# OpenLog.net
KiCad netlist of a schematic drawn in EAGLE
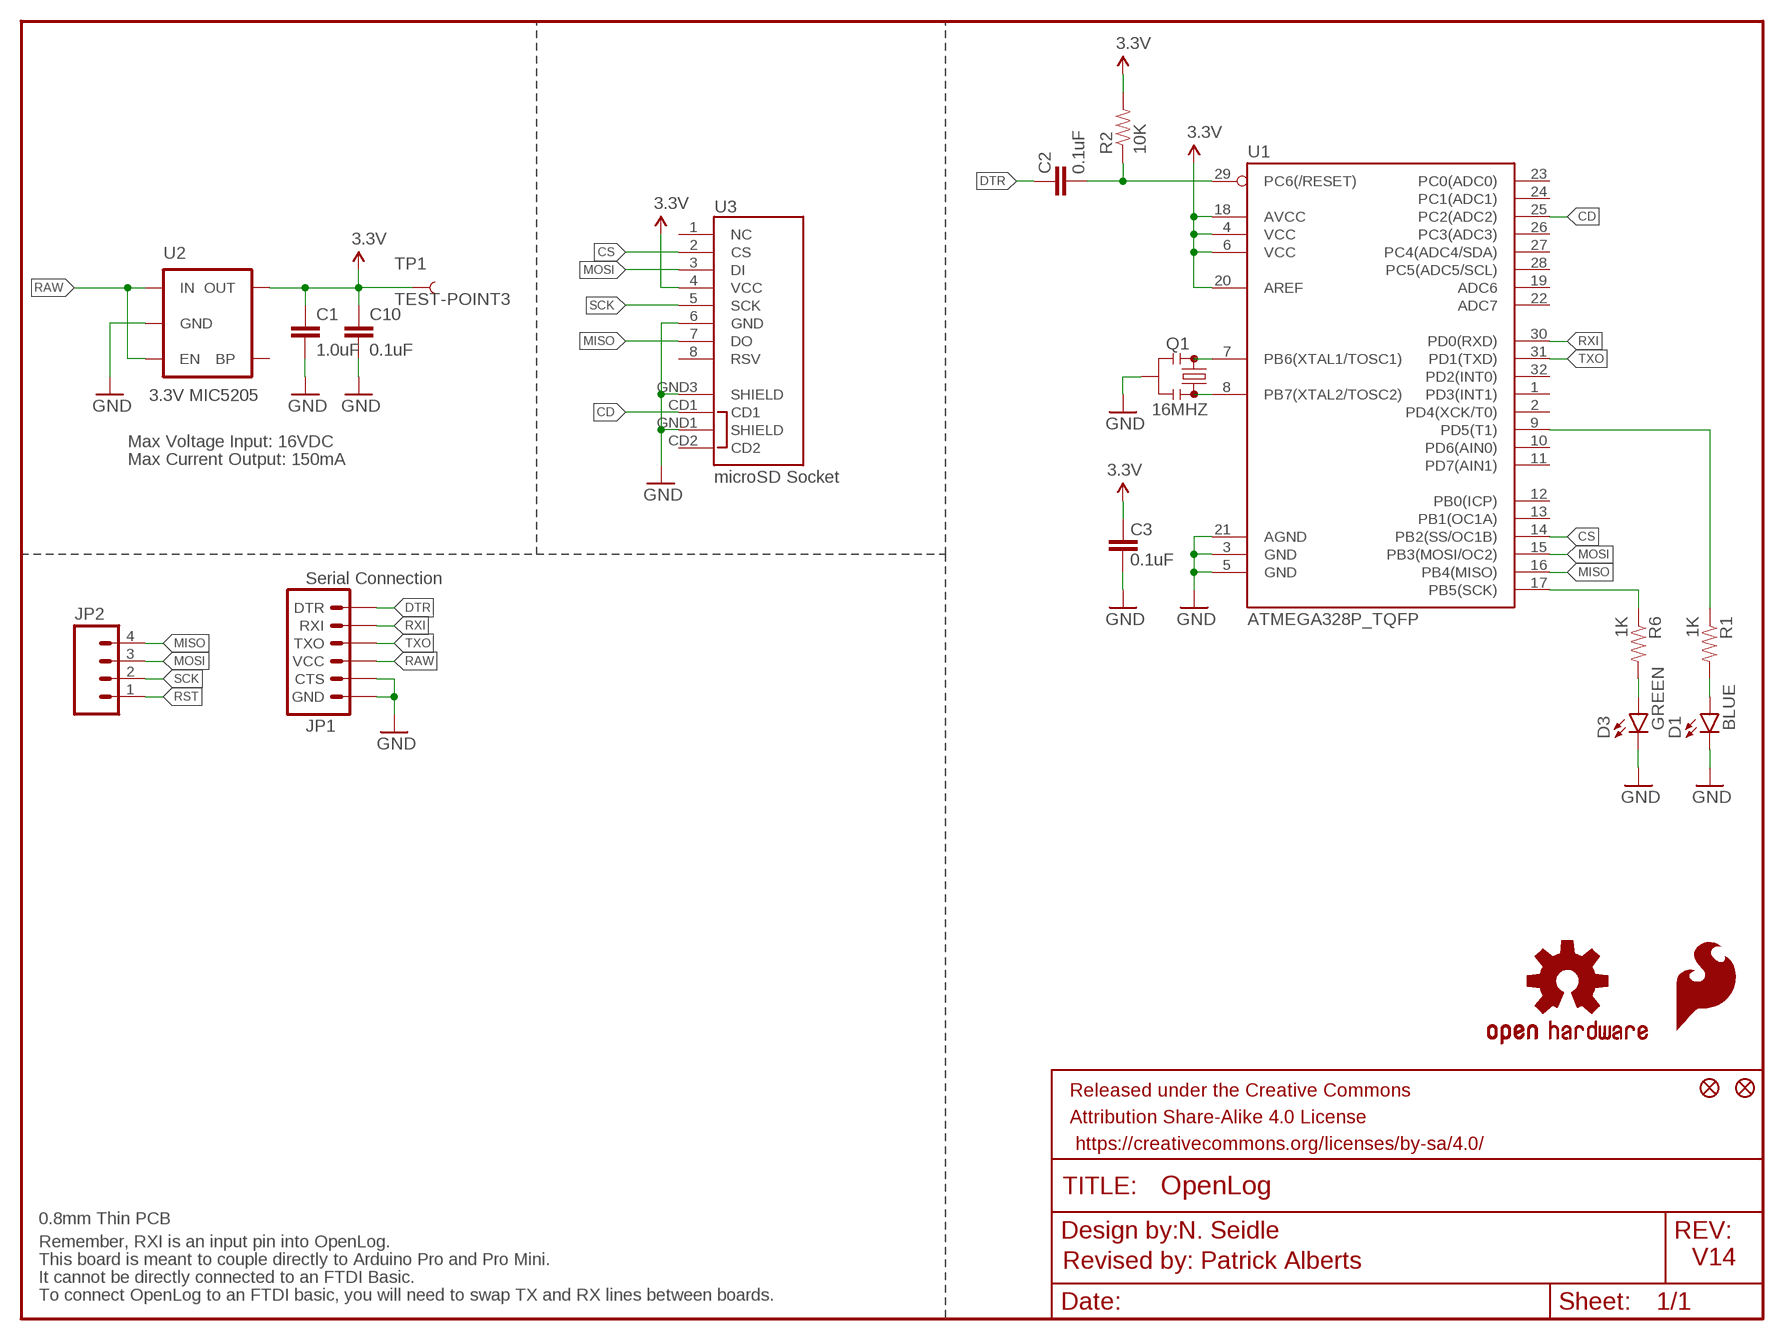
[diagram p0: schematic, sheet 1]

(export (version "E")
  (design (tool "Eeschema 10.0.6"))
  (components
    (comp (ref "C1")
      (value "1.0uF")
      (footprint "eagle-import:0603-CAP")
      (libsource (lib "eagle-import") (part "1.0UF-16V-10%(0603)"))
    )
    (comp (ref "C2")
      (value "0.1uF")
      (footprint "eagle-import:0603-CAP")
      (libsource (lib "eagle-import") (part "0.1UF-25V(+80/-20%)(0603)"))
    )
    (comp (ref "C3")
      (value "0.1uF")
      (footprint "eagle-import:0603-CAP")
      (libsource (lib "eagle-import") (part "0.1UF-25V(+80/-20%)(0603)"))
    )
    (comp (ref "C10")
      (value "0.1uF")
      (footprint "eagle-import:0603-CAP")
      (libsource (lib "eagle-import") (part "0.1UF-25V(+80/-20%)(0603)"))
    )
    (comp (ref "D1")
      (value "BLUE")
      (footprint "eagle-import:LED-0603")
      (libsource (lib "eagle-import") (part "LED-BLUE0603"))
    )
    (comp (ref "D3")
      (value "GREEN")
      (footprint "eagle-import:LED-0603")
      (libsource (lib "eagle-import") (part "LED-GREEN0603"))
    )
    (comp (ref "FID1")
      (value "FIDUCIALUFIDUCIAL")
      (footprint "eagle-import:MICRO-FIDUCIAL")
      (libsource (lib "eagle-import") (part "FIDUCIALUFIDUCIAL"))
    )
    (comp (ref "FID2")
      (value "FIDUCIALUFIDUCIAL")
      (footprint "eagle-import:MICRO-FIDUCIAL")
      (libsource (lib "eagle-import") (part "FIDUCIALUFIDUCIAL"))
    )
    (comp (ref "FRAME1")
      (value "FRAME-LETTER")
      (footprint "eagle-import:CREATIVE_COMMONS")
      (fields (field (name "DESIGNER") "NAME"))
      (libsource (lib "eagle-import") (part "FRAME-LETTER"))
    )
    (comp (ref "JP1")
      (value "Serial Connection")
      (footprint "eagle-import:1X06")
      (libsource (lib "eagle-import") (part "ARDUINO_SERIAL_PROGRAMPTH"))
    )
    (comp (ref "JP2")
      (value "M04PTH")
      (footprint "eagle-import:1X04")
      (libsource (lib "eagle-import") (part "M04PTH"))
    )
    (comp (ref "LOGO1")
      (value "SFE_LOGO_FLAME.1_INCH")
      (footprint "eagle-import:SFE_LOGO_FLAME_.1")
      (libsource (lib "eagle-import") (part "SFE_LOGO_FLAME.1_INCH"))
    )
    (comp (ref "LOGO2")
      (value "OSHW-LOGOS")
      (footprint "eagle-import:OSHW-LOGO-S")
      (libsource (lib "eagle-import") (part "OSHW-LOGOS"))
    )
    (comp (ref "Q1")
      (value "16MHZ")
      (footprint "eagle-import:RESONATOR-SMD")
      (libsource (lib "eagle-import") (part "RESONATOR16MHZ"))
    )
    (comp (ref "R1")
      (value "1K")
      (footprint "eagle-import:0603-RES")
      (libsource (lib "eagle-import") (part "1KOHM-1/10W-1%(0603)"))
    )
    (comp (ref "R2")
      (value "10K")
      (footprint "eagle-import:0603-RES")
      (libsource (lib "eagle-import") (part "10KOHM-1/10W-1%(0603)0603"))
    )
    (comp (ref "R6")
      (value "1K")
      (footprint "eagle-import:0603-RES")
      (libsource (lib "eagle-import") (part "1KOHM-1/10W-1%(0603)"))
    )
    (comp (ref "TP1")
      (value "TEST-POINT3")
      (footprint "eagle-import:PAD.03X.03")
      (libsource (lib "eagle-import") (part "TEST-POINT3"))
    )
    (comp (ref "U1")
      (value "ATMEGA328P_TQFP")
      (footprint "eagle-import:TQFP32-08")
      (libsource (lib "eagle-import") (part "ATMEGA328P_TQFP"))
    )
    (comp (ref "U2")
      (value "3.3V MIC5205")
      (footprint "eagle-import:SOT23-5")
      (libsource (lib "eagle-import") (part "MIC52053.3V"))
    )
    (comp (ref "U3")
      (value "microSD Socket")
      (footprint "eagle-import:MICROSD_1_1")
      (libsource (lib "eagle-import") (part "USD-SOCKET"))
    )
  )
  (nets
    (net (code "1") (name "3.3V") (class "Default")
      (node (ref "C1") (pin "1") (pinfunction "1_1") (pintype "passive"))
      (node (ref "C10") (pin "1") (pinfunction "1_1") (pintype "passive"))
      (node (ref "C3") (pin "2") (pinfunction "2_2") (pintype "passive"))
      (node (ref "R2") (pin "2") (pinfunction "2_2") (pintype "passive"))
      (node (ref "TP1") (pin "P$1") (pinfunction "1_P$1") (pintype "bidirectional"))
      (node (ref "U1") (pin "18") (pinfunction "AVCC_18") (pintype "bidirectional"))
      (node (ref "U1") (pin "20") (pinfunction "AREF_20") (pintype "bidirectional"))
      (node (ref "U1") (pin "4") (pinfunction "VCC_4") (pintype "bidirectional"))
      (node (ref "U1") (pin "6") (pinfunction "VCC_6") (pintype "bidirectional"))
      (node (ref "U2") (pin "5") (pinfunction "OUT_5") (pintype "passive"))
      (node (ref "U3") (pin "4") (pinfunction "VCC_4") (pintype "bidirectional"))
    )
    (net (code "2") (name "CD") (class "Default")
      (node (ref "U1") (pin "25") (pinfunction "PC2(ADC2)_25") (pintype "bidirectional"))
      (node (ref "U3") (pin "CD1") (pinfunction "CD1_CD1") (pintype "bidirectional"))
    )
    (net (code "3") (name "CS") (class "Default")
      (node (ref "U1") (pin "14") (pinfunction "PB2(SS/OC1B)_14") (pintype "bidirectional"))
      (node (ref "U3") (pin "2") (pinfunction "CS_2") (pintype "bidirectional"))
    )
    (net (code "4") (name "DTR") (class "Default")
      (node (ref "C2") (pin "2") (pinfunction "2_2") (pintype "passive"))
      (node (ref "JP1") (pin "1") (pinfunction "DTR_1") (pintype "passive"))
    )
    (net (code "5") (name "GND") (class "Default")
      (node (ref "C1") (pin "2") (pinfunction "2_2") (pintype "passive"))
      (node (ref "C10") (pin "2") (pinfunction "2_2") (pintype "passive"))
      (node (ref "C3") (pin "1") (pinfunction "1_1") (pintype "passive"))
      (node (ref "D1") (pin "C") (pinfunction "C_C") (pintype "passive"))
      (node (ref "D3") (pin "C") (pinfunction "C_C") (pintype "passive"))
      (node (ref "JP1") (pin "5") (pinfunction "CTS_5") (pintype "passive"))
      (node (ref "JP1") (pin "6") (pinfunction "GND_6") (pintype "passive"))
      (node (ref "Q1") (pin "2") (pinfunction "2_2") (pintype "passive"))
      (node (ref "U1") (pin "21") (pinfunction "AGND_21") (pintype "bidirectional"))
      (node (ref "U1") (pin "3") (pinfunction "GND_3") (pintype "bidirectional"))
      (node (ref "U1") (pin "5") (pinfunction "GND_5") (pintype "bidirectional"))
      (node (ref "U2") (pin "2") (pinfunction "GND_2") (pintype "input"))
      (node (ref "U3") (pin "6") (pinfunction "GND_6") (pintype "bidirectional"))
      (node (ref "U3") (pin "GND1") (pinfunction "SHIELD_GND1") (pintype "bidirectional"))
      (node (ref "U3") (pin "GND3") (pinfunction "SHIELD_GND3") (pintype "bidirectional"))
    )
    (net (code "6") (name "MISO") (class "Default")
      (node (ref "JP2") (pin "4") (pinfunction "4_4") (pintype "passive"))
      (node (ref "U1") (pin "16") (pinfunction "PB4(MISO)_16") (pintype "bidirectional"))
      (node (ref "U3") (pin "7") (pinfunction "DO_7") (pintype "bidirectional"))
    )
    (net (code "7") (name "MOSI") (class "Default")
      (node (ref "JP2") (pin "3") (pinfunction "3_3") (pintype "passive"))
      (node (ref "U1") (pin "15") (pinfunction "PB3(MOSI/OC2)_15") (pintype "bidirectional"))
      (node (ref "U3") (pin "3") (pinfunction "DI_3") (pintype "bidirectional"))
    )
    (net (code "8") (name "Net-(D1-PadA)") (class "Default")
      (node (ref "D1") (pin "A") (pinfunction "A_A") (pintype "passive"))
      (node (ref "R1") (pin "2") (pinfunction "2_2") (pintype "passive"))
    )
    (net (code "9") (name "Net-(D3-PadA)") (class "Default")
      (node (ref "D3") (pin "A") (pinfunction "A_A") (pintype "passive"))
      (node (ref "R6") (pin "2") (pinfunction "2_2") (pintype "passive"))
    )
    (net (code "10") (name "Net-(U1-PB6(XTAL1{slash}TOSC1))") (class "Default")
      (node (ref "Q1") (pin "3") (pinfunction "3_3") (pintype "passive"))
      (node (ref "U1") (pin "7") (pinfunction "PB6(XTAL1/TOSC1)_7") (pintype "bidirectional"))
    )
    (net (code "11") (name "Net-(U1-PB7(XTAL2{slash}TOSC2))") (class "Default")
      (node (ref "Q1") (pin "1") (pinfunction "1_1") (pintype "passive"))
      (node (ref "U1") (pin "8") (pinfunction "PB7(XTAL2/TOSC2)_8") (pintype "bidirectional"))
    )
    (net (code "12") (name "Net-(U1-PD5(T1))") (class "Default")
      (node (ref "R1") (pin "1") (pinfunction "1_1") (pintype "passive"))
      (node (ref "U1") (pin "9") (pinfunction "PD5(T1)_9") (pintype "bidirectional"))
    )
    (net (code "13") (name "RAW") (class "Default")
      (node (ref "JP1") (pin "4") (pinfunction "VCC_4") (pintype "passive"))
      (node (ref "U2") (pin "1") (pinfunction "IN_1") (pintype "input"))
      (node (ref "U2") (pin "3") (pinfunction "EN_3") (pintype "input"))
    )
    (net (code "14") (name "RST") (class "Default")
      (node (ref "C2") (pin "1") (pinfunction "1_1") (pintype "passive"))
      (node (ref "JP2") (pin "1") (pinfunction "1_1") (pintype "passive"))
      (node (ref "R2") (pin "1") (pinfunction "1_1") (pintype "passive"))
      (node (ref "U1") (pin "29") (pinfunction "PC6(/RESET)_29") (pintype "bidirectional"))
    )
    (net (code "15") (name "RXI") (class "Default")
      (node (ref "JP1") (pin "2") (pinfunction "RXI_2") (pintype "passive"))
      (node (ref "U1") (pin "30") (pinfunction "PD0(RXD)_30") (pintype "bidirectional"))
    )
    (net (code "16") (name "SCK") (class "Default")
      (node (ref "JP2") (pin "2") (pinfunction "2_2") (pintype "passive"))
      (node (ref "R6") (pin "1") (pinfunction "1_1") (pintype "passive"))
      (node (ref "U1") (pin "17") (pinfunction "PB5(SCK)_17") (pintype "bidirectional"))
      (node (ref "U3") (pin "5") (pinfunction "SCK_5") (pintype "bidirectional"))
    )
    (net (code "17") (name "TXO") (class "Default")
      (node (ref "JP1") (pin "3") (pinfunction "TXO_3") (pintype "passive"))
      (node (ref "U1") (pin "31") (pinfunction "PD1(TXD)_31") (pintype "bidirectional"))
    )
    (net (code "18") (name "unconnected-(U1-ADC6-Pad19)") (class "Default")
      (node (ref "U1") (pin "19") (pinfunction "ADC6_19") (pintype "bidirectional"))
    )
    (net (code "19") (name "unconnected-(U1-ADC7-Pad22)") (class "Default")
      (node (ref "U1") (pin "22") (pinfunction "ADC7_22") (pintype "bidirectional"))
    )
    (net (code "20") (name "unconnected-(U1-PB0(ICP)-Pad12)") (class "Default")
      (node (ref "U1") (pin "12") (pinfunction "PB0(ICP)_12") (pintype "bidirectional"))
    )
    (net (code "21") (name "unconnected-(U1-PB1(OC1A)-Pad13)") (class "Default")
      (node (ref "U1") (pin "13") (pinfunction "PB1(OC1A)_13") (pintype "bidirectional"))
    )
    (net (code "22") (name "unconnected-(U1-PC0(ADC0)-Pad23)") (class "Default")
      (node (ref "U1") (pin "23") (pinfunction "PC0(ADC0)_23") (pintype "bidirectional"))
    )
    (net (code "23") (name "unconnected-(U1-PC1(ADC1)-Pad24)") (class "Default")
      (node (ref "U1") (pin "24") (pinfunction "PC1(ADC1)_24") (pintype "bidirectional"))
    )
    (net (code "24") (name "unconnected-(U1-PC3(ADC3)-Pad26)") (class "Default")
      (node (ref "U1") (pin "26") (pinfunction "PC3(ADC3)_26") (pintype "bidirectional"))
    )
    (net (code "25") (name "unconnected-(U1-PC4(ADC4{slash}SDA)-Pad27)") (class "Default")
      (node (ref "U1") (pin "27") (pinfunction "PC4(ADC4/SDA)_27") (pintype "bidirectional"))
    )
    (net (code "26") (name "unconnected-(U1-PC5(ADC5{slash}SCL)-Pad28)") (class "Default")
      (node (ref "U1") (pin "28") (pinfunction "PC5(ADC5/SCL)_28") (pintype "bidirectional"))
    )
    (net (code "27") (name "unconnected-(U1-PD2(INT0)-Pad32)") (class "Default")
      (node (ref "U1") (pin "32") (pinfunction "PD2(INT0)_32") (pintype "bidirectional"))
    )
    (net (code "28") (name "unconnected-(U1-PD3(INT1)-Pad1)") (class "Default")
      (node (ref "U1") (pin "1") (pinfunction "PD3(INT1)_1") (pintype "bidirectional"))
    )
    (net (code "29") (name "unconnected-(U1-PD4(XCK{slash}T0)-Pad2)") (class "Default")
      (node (ref "U1") (pin "2") (pinfunction "PD4(XCK/T0)_2") (pintype "bidirectional"))
    )
    (net (code "30") (name "unconnected-(U1-PD6(AIN0)-Pad10)") (class "Default")
      (node (ref "U1") (pin "10") (pinfunction "PD6(AIN0)_10") (pintype "bidirectional"))
    )
    (net (code "31") (name "unconnected-(U1-PD7(AIN1)-Pad11)") (class "Default")
      (node (ref "U1") (pin "11") (pinfunction "PD7(AIN1)_11") (pintype "bidirectional"))
    )
    (net (code "32") (name "unconnected-(U2-BP-Pad4)") (class "Default")
      (node (ref "U2") (pin "4") (pinfunction "BP_4") (pintype "input"))
    )
    (net (code "33") (name "unconnected-(U3-NC-Pad1)") (class "Default")
      (node (ref "U3") (pin "1") (pinfunction "NC_1") (pintype "bidirectional"))
    )
    (net (code "34") (name "unconnected-(U3-PadCD2)") (class "Default")
      (node (ref "U3") (pin "CD2") (pinfunction "CD2_CD2") (pintype "bidirectional"))
    )
    (net (code "35") (name "unconnected-(U3-RSV-Pad8)") (class "Default")
      (node (ref "U3") (pin "8") (pinfunction "RSV_8") (pintype "bidirectional"))
    )
  )
)
